# TSAL_ON_BRIAN_BOARD.net
KiCad netlist of a schematic drawn in EAGLE
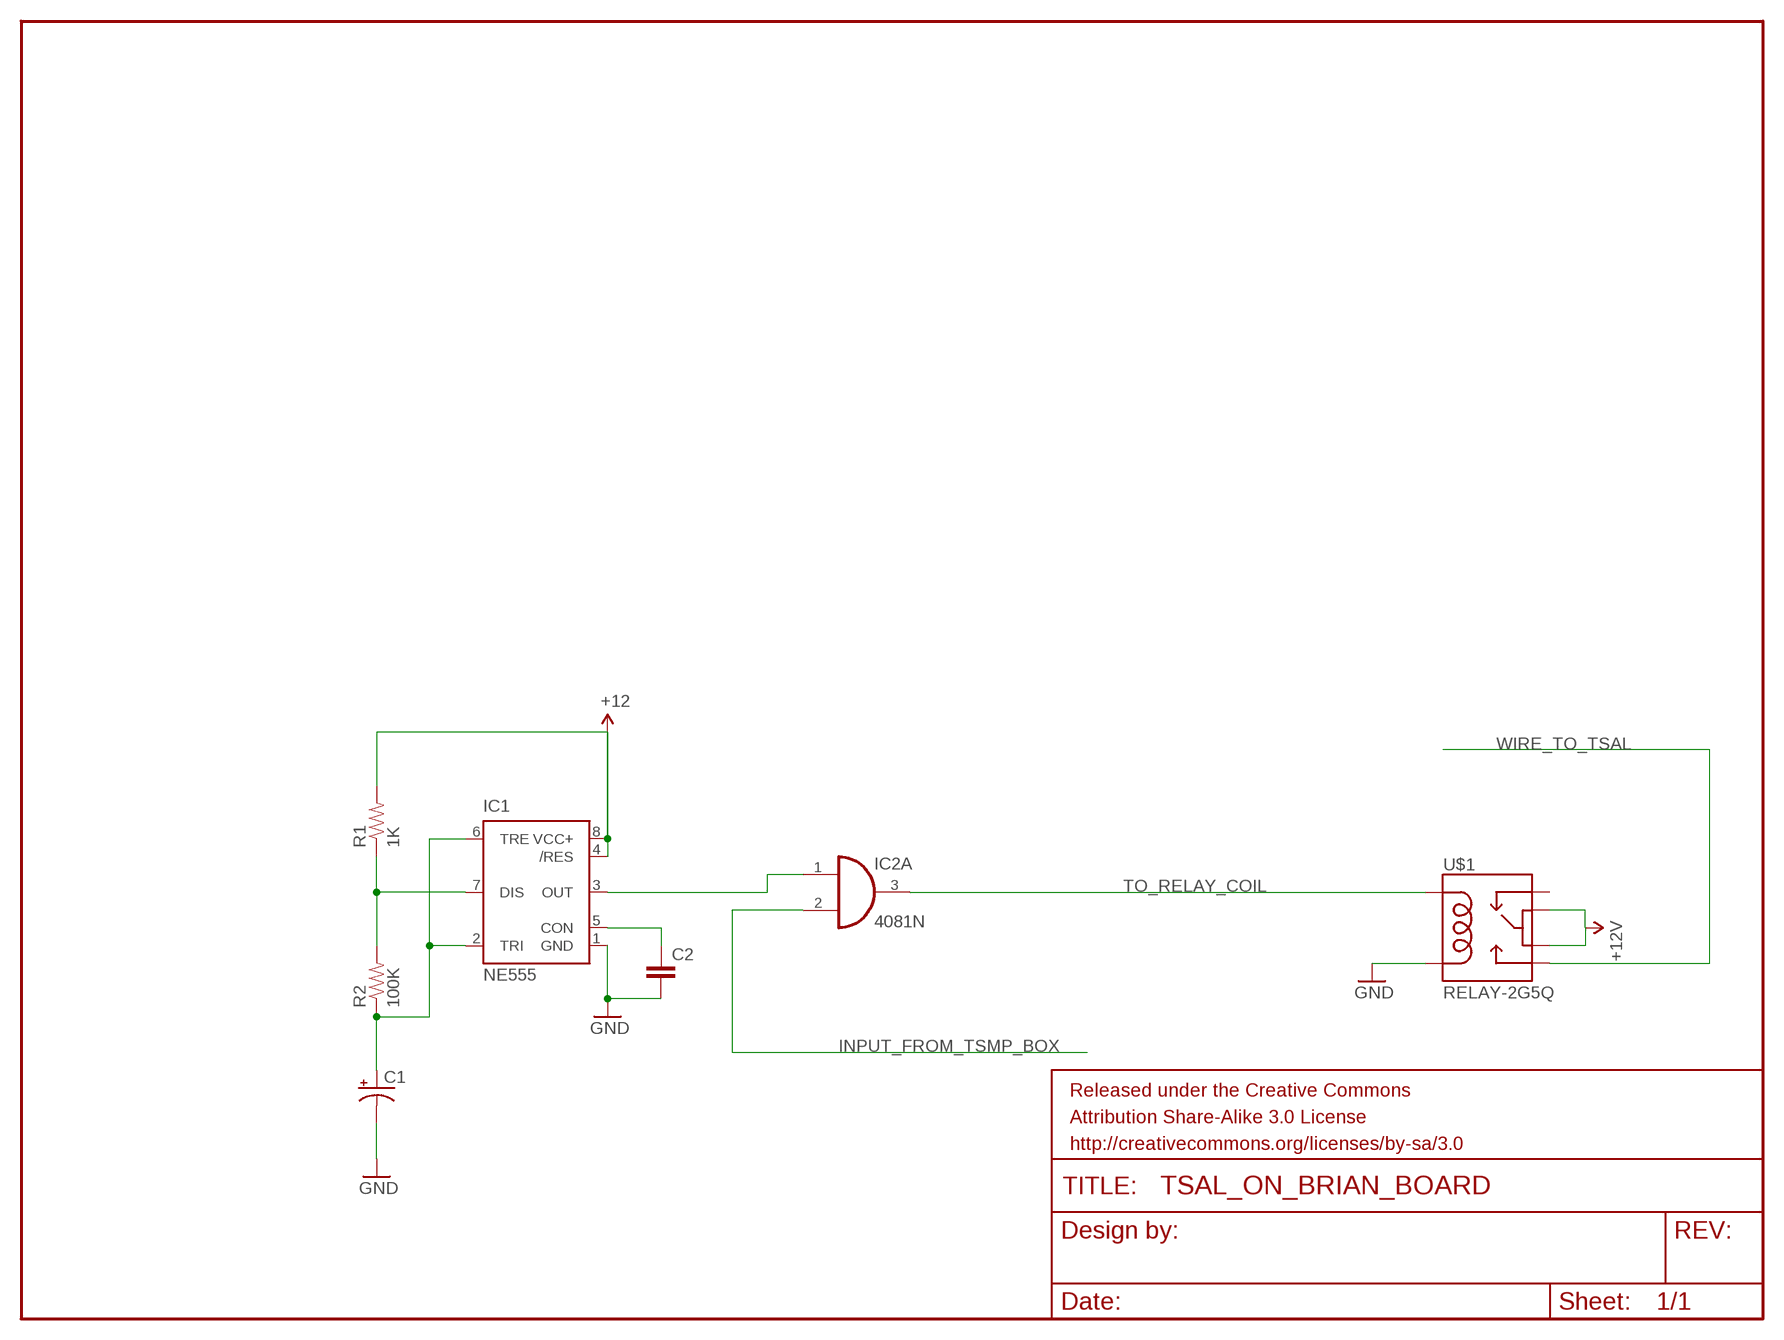
[diagram p0: schematic, sheet 1]

(export (version "E")
  (design (tool "Eeschema 10.0.6"))
  (components
    (comp (ref "C1")
      (value "CAP_POLPTH1")
      (footprint "eagle-import:CPOL-RADIAL-100UF-25V")
      (libsource (lib "eagle-import") (part "CAP_POLPTH1"))
    )
    (comp (ref "C2")
      (value "CAPPTH2")
      (footprint "eagle-import:CAP-PTH-SMALL2")
      (libsource (lib "eagle-import") (part "CAPPTH2"))
    )
    (comp (ref "FRAME1")
      (value "FRAME-LETTER")
      (footprint "eagle-import:CREATIVE_COMMONS")
      (libsource (lib "eagle-import") (part "FRAME-LETTER"))
    )
    (comp (ref "IC1")
      (value "NE555")
      (footprint "eagle-import:DIL-08")
      (fields (field (name "MF") "Arrow Electronics") (field (name "MPN") "NE555N"))
      (libsource (lib "eagle-import") (part "NE555"))
    )
    (comp (ref "IC2")
      (value "4081N")
      (footprint "eagle-import:DIL14")
      (libsource (lib "eagle-import") (part "4081N"))
    )
    (comp (ref "R1")
      (value "1K")
      (footprint "eagle-import:AXIAL-0.3EZ")
      (libsource (lib "eagle-import") (part "RESISTOREZ"))
    )
    (comp (ref "R2")
      (value "100K")
      (footprint "eagle-import:AXIAL-0.3EZ")
      (libsource (lib "eagle-import") (part "RESISTOREZ"))
    )
    (comp (ref "U$1")
      (value "RELAY-2G5Q")
      (footprint "eagle-import:RELAY-G5V")
      (libsource (lib "eagle-import") (part "RELAY-2G5Q"))
    )
  )
  (nets
    (net (code "1") (name "+12") (class "Default")
      (node (ref "IC1") (pin "4") (pinfunction "/RES_4") (pintype "input"))
      (node (ref "IC1") (pin "8") (pinfunction "VCC+_8") (pintype "power_in"))
      (node (ref "R1") (pin "P$2") (pinfunction "2_P$2") (pintype "passive"))
      (node (ref "U$1") (pin "5") (pinfunction "5_5") (pintype "bidirectional"))
      (node (ref "U$1") (pin "6") (pinfunction "6_6") (pintype "bidirectional"))
    )
    (net (code "2") (name "/INPUT_FROM_TSMP_BOX") (class "Default")
      (node (ref "IC2") (pin "2") (pinfunction "I1_2") (pintype "input"))
    )
    (net (code "3") (name "/TO_RELAY_COIL") (class "Default")
      (node (ref "IC2") (pin "3") (pinfunction "O_3") (pintype "output"))
      (node (ref "U$1") (pin "2") (pinfunction "2_2") (pintype "bidirectional"))
    )
    (net (code "4") (name "/WIRE_TO_TSAL") (class "Default")
      (node (ref "U$1") (pin "10") (pinfunction "10_10") (pintype "bidirectional"))
    )
    (net (code "5") (name "GND") (class "Default")
      (node (ref "C1") (pin "2") (pinfunction "-_2") (pintype "passive"))
      (node (ref "C2") (pin "2") (pinfunction "2_2") (pintype "passive"))
      (node (ref "IC1") (pin "1") (pinfunction "GND_1") (pintype "power_in"))
      (node (ref "U$1") (pin "9") (pinfunction "9_9") (pintype "bidirectional"))
    )
    (net (code "6") (name "Net-(C1-+)") (class "Default")
      (node (ref "C1") (pin "1") (pinfunction "+_1") (pintype "passive"))
      (node (ref "IC1") (pin "2") (pinfunction "TRI_2") (pintype "input"))
      (node (ref "IC1") (pin "6") (pinfunction "TRE_6") (pintype "input"))
      (node (ref "R2") (pin "P$1") (pinfunction "1_P$1") (pintype "passive"))
    )
    (net (code "7") (name "Net-(IC1-CON)") (class "Default")
      (node (ref "C2") (pin "1") (pinfunction "1_1") (pintype "passive"))
      (node (ref "IC1") (pin "5") (pinfunction "CON_5") (pintype "input"))
    )
    (net (code "8") (name "Net-(IC1-DIS)") (class "Default")
      (node (ref "IC1") (pin "7") (pinfunction "DIS_7") (pintype "input"))
      (node (ref "R1") (pin "P$1") (pinfunction "1_P$1") (pintype "passive"))
      (node (ref "R2") (pin "P$2") (pinfunction "2_P$2") (pintype "passive"))
    )
    (net (code "9") (name "Net-(IC1-OUT)") (class "Default")
      (node (ref "IC1") (pin "3") (pinfunction "OUT_3") (pintype "output"))
      (node (ref "IC2") (pin "1") (pinfunction "I0_1") (pintype "input"))
    )
    (net (code "10") (name "unconnected-(U$1-Pad1)") (class "Default")
      (node (ref "U$1") (pin "1") (pinfunction "1_1") (pintype "bidirectional"))
    )
  )
)
